# D_amplifier.net
KiCad netlist of a schematic drawn in EAGLE
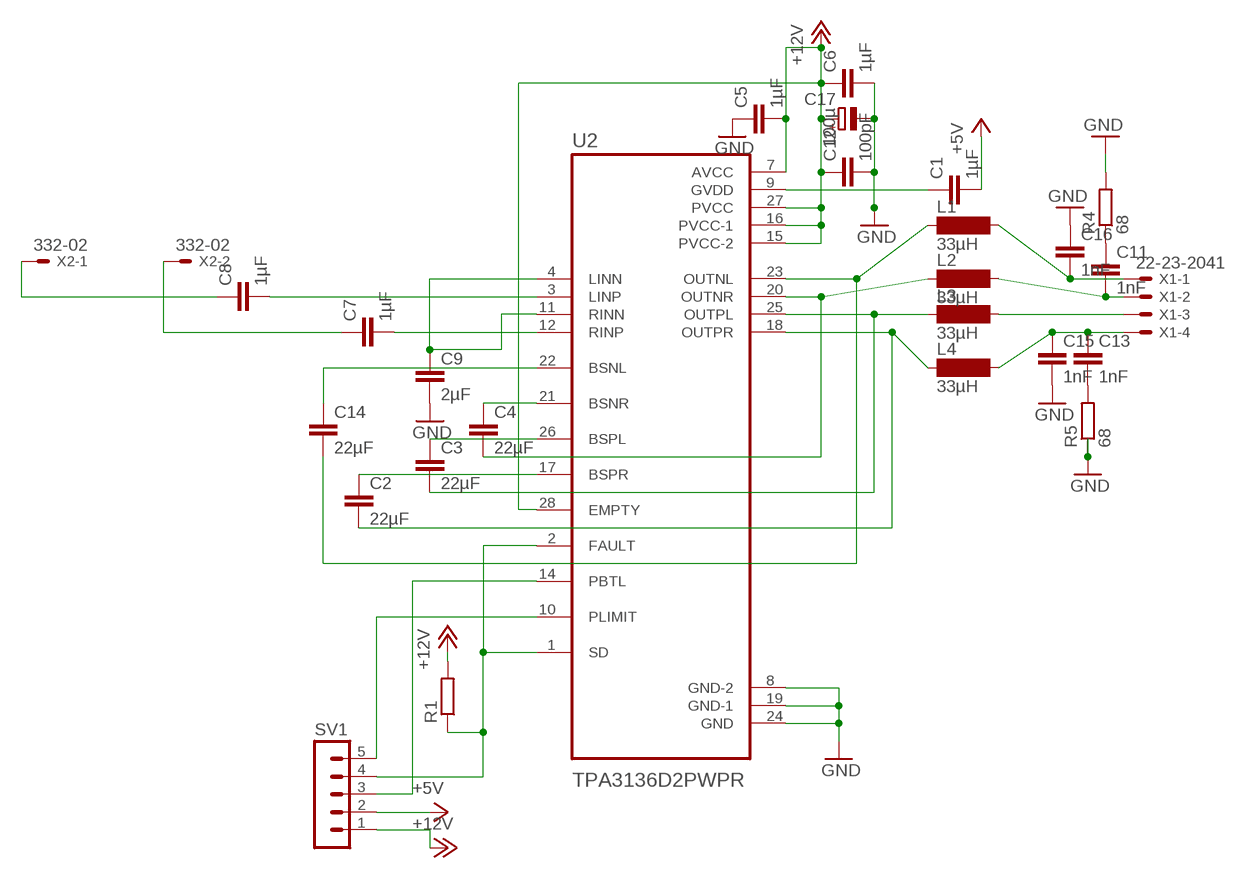
[diagram p0: schematic, sheet 1]

(export (version "E")
  (design (tool "Eeschema 10.0.6"))
  (components
    (comp (ref "C1")
      (value "1µF")
      (footprint "eagle-import:C0805K")
      (libsource (lib "eagle-import") (part "C-EUC0805K"))
    )
    (comp (ref "C2")
      (value "22µF")
      (footprint "eagle-import:C0805K")
      (libsource (lib "eagle-import") (part "C-EUC0805K"))
    )
    (comp (ref "C3")
      (value "22µF")
      (footprint "eagle-import:C0805K")
      (libsource (lib "eagle-import") (part "C-EUC0805K"))
    )
    (comp (ref "C4")
      (value "22µF")
      (footprint "eagle-import:C0805K")
      (libsource (lib "eagle-import") (part "C-EUC0805K"))
    )
    (comp (ref "C5")
      (value "1µF")
      (footprint "eagle-import:C0805K")
      (libsource (lib "eagle-import") (part "C-EUC0805K"))
    )
    (comp (ref "C6")
      (value "1µF")
      (footprint "eagle-import:C0805K")
      (libsource (lib "eagle-import") (part "C-EUC0805K"))
    )
    (comp (ref "C7")
      (value "1µF")
      (footprint "eagle-import:C0805K")
      (libsource (lib "eagle-import") (part "C-EUC0805K"))
    )
    (comp (ref "C8")
      (value "1µF")
      (footprint "eagle-import:C0805K")
      (libsource (lib "eagle-import") (part "C-EUC0805K"))
    )
    (comp (ref "C9")
      (value "2µF")
      (footprint "eagle-import:C0805K")
      (libsource (lib "eagle-import") (part "C-EUC0805K"))
    )
    (comp (ref "C11")
      (value "1nF")
      (footprint "eagle-import:C0805K")
      (libsource (lib "eagle-import") (part "C-EUC0805K"))
    )
    (comp (ref "C12")
      (value "100pF")
      (footprint "eagle-import:C0805K")
      (libsource (lib "eagle-import") (part "C-EUC0805K"))
    )
    (comp (ref "C13")
      (value "1nF")
      (footprint "eagle-import:C0805K")
      (libsource (lib "eagle-import") (part "C-EUC0805K"))
    )
    (comp (ref "C14")
      (value "22µF")
      (footprint "eagle-import:C0805K")
      (libsource (lib "eagle-import") (part "C-EUC0805K"))
    )
    (comp (ref "C15")
      (value "1nF")
      (footprint "eagle-import:C0805K")
      (libsource (lib "eagle-import") (part "C-EUC0805K"))
    )
    (comp (ref "C16")
      (value "1nF")
      (footprint "eagle-import:C0805K")
      (libsource (lib "eagle-import") (part "C-EUC0805K"))
    )
    (comp (ref "C17")
      (value "100µ")
      (footprint "eagle-import:085CS_1AR")
      (libsource (lib "eagle-import") (part "CPOL-EU085CS-1AR"))
    )
    (comp (ref "L1")
      (value "33µH")
      (footprint "eagle-import:SD12-680")
      (fields (field (name "MF") "BUSSMANN") (field (name "MPN") "SD12-680"))
      (libsource (lib "eagle-import") (part "SD12-680"))
    )
    (comp (ref "L2")
      (value "33µH")
      (footprint "eagle-import:SD12-680")
      (fields (field (name "MF") "BUSSMANN") (field (name "MPN") "SD12-680"))
      (libsource (lib "eagle-import") (part "SD12-680"))
    )
    (comp (ref "L3")
      (value "33µH")
      (footprint "eagle-import:SD12-680")
      (fields (field (name "MF") "BUSSMANN") (field (name "MPN") "SD12-680"))
      (libsource (lib "eagle-import") (part "SD12-680"))
    )
    (comp (ref "L4")
      (value "33µH")
      (footprint "eagle-import:SD12-680")
      (fields (field (name "MF") "BUSSMANN") (field (name "MPN") "SD12-680"))
      (libsource (lib "eagle-import") (part "SD12-680"))
    )
    (comp (ref "R1")
      (value "R-EU_R0805")
      (footprint "eagle-import:R0805")
      (libsource (lib "eagle-import") (part "R-EU_R0805"))
    )
    (comp (ref "R4")
      (value "68")
      (footprint "eagle-import:M0805")
      (libsource (lib "eagle-import") (part "R-EU_M0805"))
    )
    (comp (ref "R5")
      (value "68")
      (footprint "eagle-import:M0805")
      (libsource (lib "eagle-import") (part "R-EU_M0805"))
    )
    (comp (ref "SV1")
      (value "MA05-1")
      (footprint "eagle-import:MA05-1")
      (libsource (lib "eagle-import") (part "MA05-1"))
    )
    (comp (ref "U2")
      (value "TPA3136D2PWPR")
      (footprint "eagle-import:IC_TPS61196PWPRQ1")
      (fields (field (name "MF") "Texas Instruments"))
      (libsource (lib "eagle-import") (part "TPA3136D2PWPR"))
    )
    (comp (ref "X1")
      (value "22-23-2041")
      (footprint "eagle-import:22-23-2041")
      (fields (field (name "MF") "MOLEX"))
      (libsource (lib "eagle-import") (part "22-23-2041"))
    )
    (comp (ref "X2")
      (value "332-02")
      (footprint "eagle-import:332-02")
      (libsource (lib "eagle-import") (part "332-02"))
    )
  )
  (nets
    (net (code "1") (name "+5V") (class "Default")
      (node (ref "C1") (pin "2") (pinfunction "2_2") (pintype "passive"))
      (node (ref "SV1") (pin "2") (pinfunction "2_2") (pintype "passive"))
    )
    (net (code "2") (name "+12V") (class "Default")
      (node (ref "C12") (pin "1") (pinfunction "1_1") (pintype "passive"))
      (node (ref "C17") (pin "+") (pinfunction "+_+") (pintype "passive"))
      (node (ref "C5") (pin "2") (pinfunction "2_2") (pintype "passive"))
      (node (ref "C6") (pin "1") (pinfunction "1_1") (pintype "passive"))
      (node (ref "R1") (pin "2") (pinfunction "2_2") (pintype "passive"))
      (node (ref "SV1") (pin "1") (pinfunction "1_1") (pintype "passive"))
      (node (ref "U2") (pin "15") (pinfunction "PVCC-2_15") (pintype "power_in"))
      (node (ref "U2") (pin "16") (pinfunction "PVCC-1_16") (pintype "power_in"))
      (node (ref "U2") (pin "27") (pinfunction "PVCC_27") (pintype "power_in"))
      (node (ref "U2") (pin "28") (pinfunction "EMPTY_28") (pintype "bidirectional"))
      (node (ref "U2") (pin "7") (pinfunction "AVCC_7") (pintype "power_in"))
    )
    (net (code "3") (name "GND") (class "Default")
      (node (ref "C12") (pin "2") (pinfunction "2_2") (pintype "passive"))
      (node (ref "C15") (pin "2") (pinfunction "2_2") (pintype "passive"))
      (node (ref "C16") (pin "1") (pinfunction "1_1") (pintype "passive"))
      (node (ref "C17") (pin "-") (pinfunction "-_-") (pintype "passive"))
      (node (ref "C5") (pin "1") (pinfunction "1_1") (pintype "passive"))
      (node (ref "C6") (pin "2") (pinfunction "2_2") (pintype "passive"))
      (node (ref "C9") (pin "2") (pinfunction "2_2") (pintype "passive"))
      (node (ref "R4") (pin "2") (pinfunction "2_2") (pintype "passive"))
      (node (ref "R5") (pin "1") (pinfunction "1_1") (pintype "passive"))
      (node (ref "U2") (pin "19") (pinfunction "GND-1_19") (pintype "power_in"))
      (node (ref "U2") (pin "24") (pinfunction "GND_24") (pintype "power_in"))
      (node (ref "U2") (pin "8") (pinfunction "GND-2_8") (pintype "power_in"))
    )
    (net (code "4") (name "Net-(C11-Pad1)") (class "Default")
      (node (ref "C11") (pin "1") (pinfunction "1_1") (pintype "passive"))
      (node (ref "R4") (pin "1") (pinfunction "1_1") (pintype "passive"))
    )
    (net (code "5") (name "Net-(C13-Pad2)") (class "Default")
      (node (ref "C13") (pin "2") (pinfunction "2_2") (pintype "passive"))
      (node (ref "R5") (pin "2") (pinfunction "2_2") (pintype "passive"))
    )
    (net (code "6") (name "Net-(U2-BSNL)") (class "Default")
      (node (ref "C14") (pin "1") (pinfunction "1_1") (pintype "passive"))
      (node (ref "U2") (pin "22") (pinfunction "BSNL_22") (pintype "bidirectional"))
    )
    (net (code "7") (name "Net-(U2-BSNR)") (class "Default")
      (node (ref "C4") (pin "1") (pinfunction "1_1") (pintype "passive"))
      (node (ref "U2") (pin "21") (pinfunction "BSNR_21") (pintype "bidirectional"))
    )
    (net (code "8") (name "Net-(U2-BSPL)") (class "Default")
      (node (ref "C3") (pin "1") (pinfunction "1_1") (pintype "passive"))
      (node (ref "U2") (pin "26") (pinfunction "BSPL_26") (pintype "bidirectional"))
    )
    (net (code "9") (name "Net-(U2-BSPR)") (class "Default")
      (node (ref "C2") (pin "1") (pinfunction "1_1") (pintype "passive"))
      (node (ref "U2") (pin "17") (pinfunction "BSPR_17") (pintype "bidirectional"))
    )
    (net (code "10") (name "Net-(U2-FAULT)") (class "Default")
      (node (ref "R1") (pin "1") (pinfunction "1_1") (pintype "passive"))
      (node (ref "SV1") (pin "4") (pinfunction "4_4") (pintype "passive"))
      (node (ref "U2") (pin "1") (pinfunction "SD_1") (pintype "bidirectional"))
      (node (ref "U2") (pin "2") (pinfunction "FAULT_2") (pintype "bidirectional"))
    )
    (net (code "11") (name "Net-(U2-GVDD)") (class "Default")
      (node (ref "C1") (pin "1") (pinfunction "1_1") (pintype "passive"))
      (node (ref "U2") (pin "9") (pinfunction "GVDD_9") (pintype "power_in"))
    )
    (net (code "12") (name "Net-(U2-LINN)") (class "Default")
      (node (ref "C9") (pin "1") (pinfunction "1_1") (pintype "passive"))
      (node (ref "U2") (pin "11") (pinfunction "RINN_11") (pintype "input"))
      (node (ref "U2") (pin "4") (pinfunction "LINN_4") (pintype "input"))
    )
    (net (code "13") (name "Net-(U2-LINP)") (class "Default")
      (node (ref "C8") (pin "2") (pinfunction "2_2") (pintype "passive"))
      (node (ref "U2") (pin "3") (pinfunction "LINP_3") (pintype "input"))
    )
    (net (code "14") (name "Net-(U2-OUTNL)") (class "Default")
      (node (ref "C14") (pin "2") (pinfunction "2_2") (pintype "passive"))
      (node (ref "L1") (pin "1") (pinfunction "1_1") (pintype "passive"))
      (node (ref "U2") (pin "23") (pinfunction "OUTNL_23") (pintype "output"))
    )
    (net (code "15") (name "Net-(U2-OUTNR)") (class "Default")
      (node (ref "C4") (pin "2") (pinfunction "2_2") (pintype "passive"))
      (node (ref "L2") (pin "1") (pinfunction "1_1") (pintype "passive"))
      (node (ref "U2") (pin "20") (pinfunction "OUTNR_20") (pintype "output"))
    )
    (net (code "16") (name "Net-(U2-OUTPL)") (class "Default")
      (node (ref "C3") (pin "2") (pinfunction "2_2") (pintype "passive"))
      (node (ref "L3") (pin "1") (pinfunction "1_1") (pintype "passive"))
      (node (ref "U2") (pin "25") (pinfunction "OUTPL_25") (pintype "output"))
    )
    (net (code "17") (name "Net-(U2-OUTPR)") (class "Default")
      (node (ref "C2") (pin "2") (pinfunction "2_2") (pintype "passive"))
      (node (ref "L4") (pin "1") (pinfunction "1_1") (pintype "passive"))
      (node (ref "U2") (pin "18") (pinfunction "OUTPR_18") (pintype "output"))
    )
    (net (code "18") (name "Net-(U2-PBTL)") (class "Default")
      (node (ref "SV1") (pin "3") (pinfunction "3_3") (pintype "passive"))
      (node (ref "U2") (pin "14") (pinfunction "PBTL_14") (pintype "bidirectional"))
    )
    (net (code "19") (name "Net-(U2-PLIMIT)") (class "Default")
      (node (ref "SV1") (pin "5") (pinfunction "5_5") (pintype "passive"))
      (node (ref "U2") (pin "10") (pinfunction "PLIMIT_10") (pintype "bidirectional"))
    )
    (net (code "20") (name "Net-(U2-RINP)") (class "Default")
      (node (ref "C7") (pin "2") (pinfunction "2_2") (pintype "passive"))
      (node (ref "U2") (pin "12") (pinfunction "RINP_12") (pintype "input"))
    )
    (net (code "21") (name "Net-(X1A-S)") (class "Default")
      (node (ref "C16") (pin "2") (pinfunction "2_2") (pintype "passive"))
      (node (ref "L1") (pin "2") (pinfunction "2_2") (pintype "passive"))
      (node (ref "X1") (pin "1") (pinfunction "S_1") (pintype "passive"))
    )
    (net (code "22") (name "Net-(X1B-S)") (class "Default")
      (node (ref "C11") (pin "2") (pinfunction "2_2") (pintype "passive"))
      (node (ref "L2") (pin "2") (pinfunction "2_2") (pintype "passive"))
      (node (ref "X1") (pin "2") (pinfunction "S_2") (pintype "passive"))
    )
    (net (code "23") (name "Net-(X1C-S)") (class "Default")
      (node (ref "L3") (pin "2") (pinfunction "2_2") (pintype "passive"))
      (node (ref "X1") (pin "3") (pinfunction "S_3") (pintype "passive"))
    )
    (net (code "24") (name "Net-(X1D-S)") (class "Default")
      (node (ref "C13") (pin "1") (pinfunction "1_1") (pintype "passive"))
      (node (ref "C15") (pin "1") (pinfunction "1_1") (pintype "passive"))
      (node (ref "L4") (pin "2") (pinfunction "2_2") (pintype "passive"))
      (node (ref "X1") (pin "4") (pinfunction "S_4") (pintype "passive"))
    )
    (net (code "25") (name "Net-(X2A-S)") (class "Default")
      (node (ref "C8") (pin "1") (pinfunction "1_1") (pintype "passive"))
      (node (ref "X2") (pin "1") (pinfunction "S_1") (pintype "passive"))
    )
    (net (code "26") (name "Net-(X2B-S)") (class "Default")
      (node (ref "C7") (pin "1") (pinfunction "1_1") (pintype "passive"))
      (node (ref "X2") (pin "2") (pinfunction "S_2") (pintype "passive"))
    )
  )
)
